# B_Main_board_v1_3.net
KiCad netlist of a schematic drawn in EAGLE
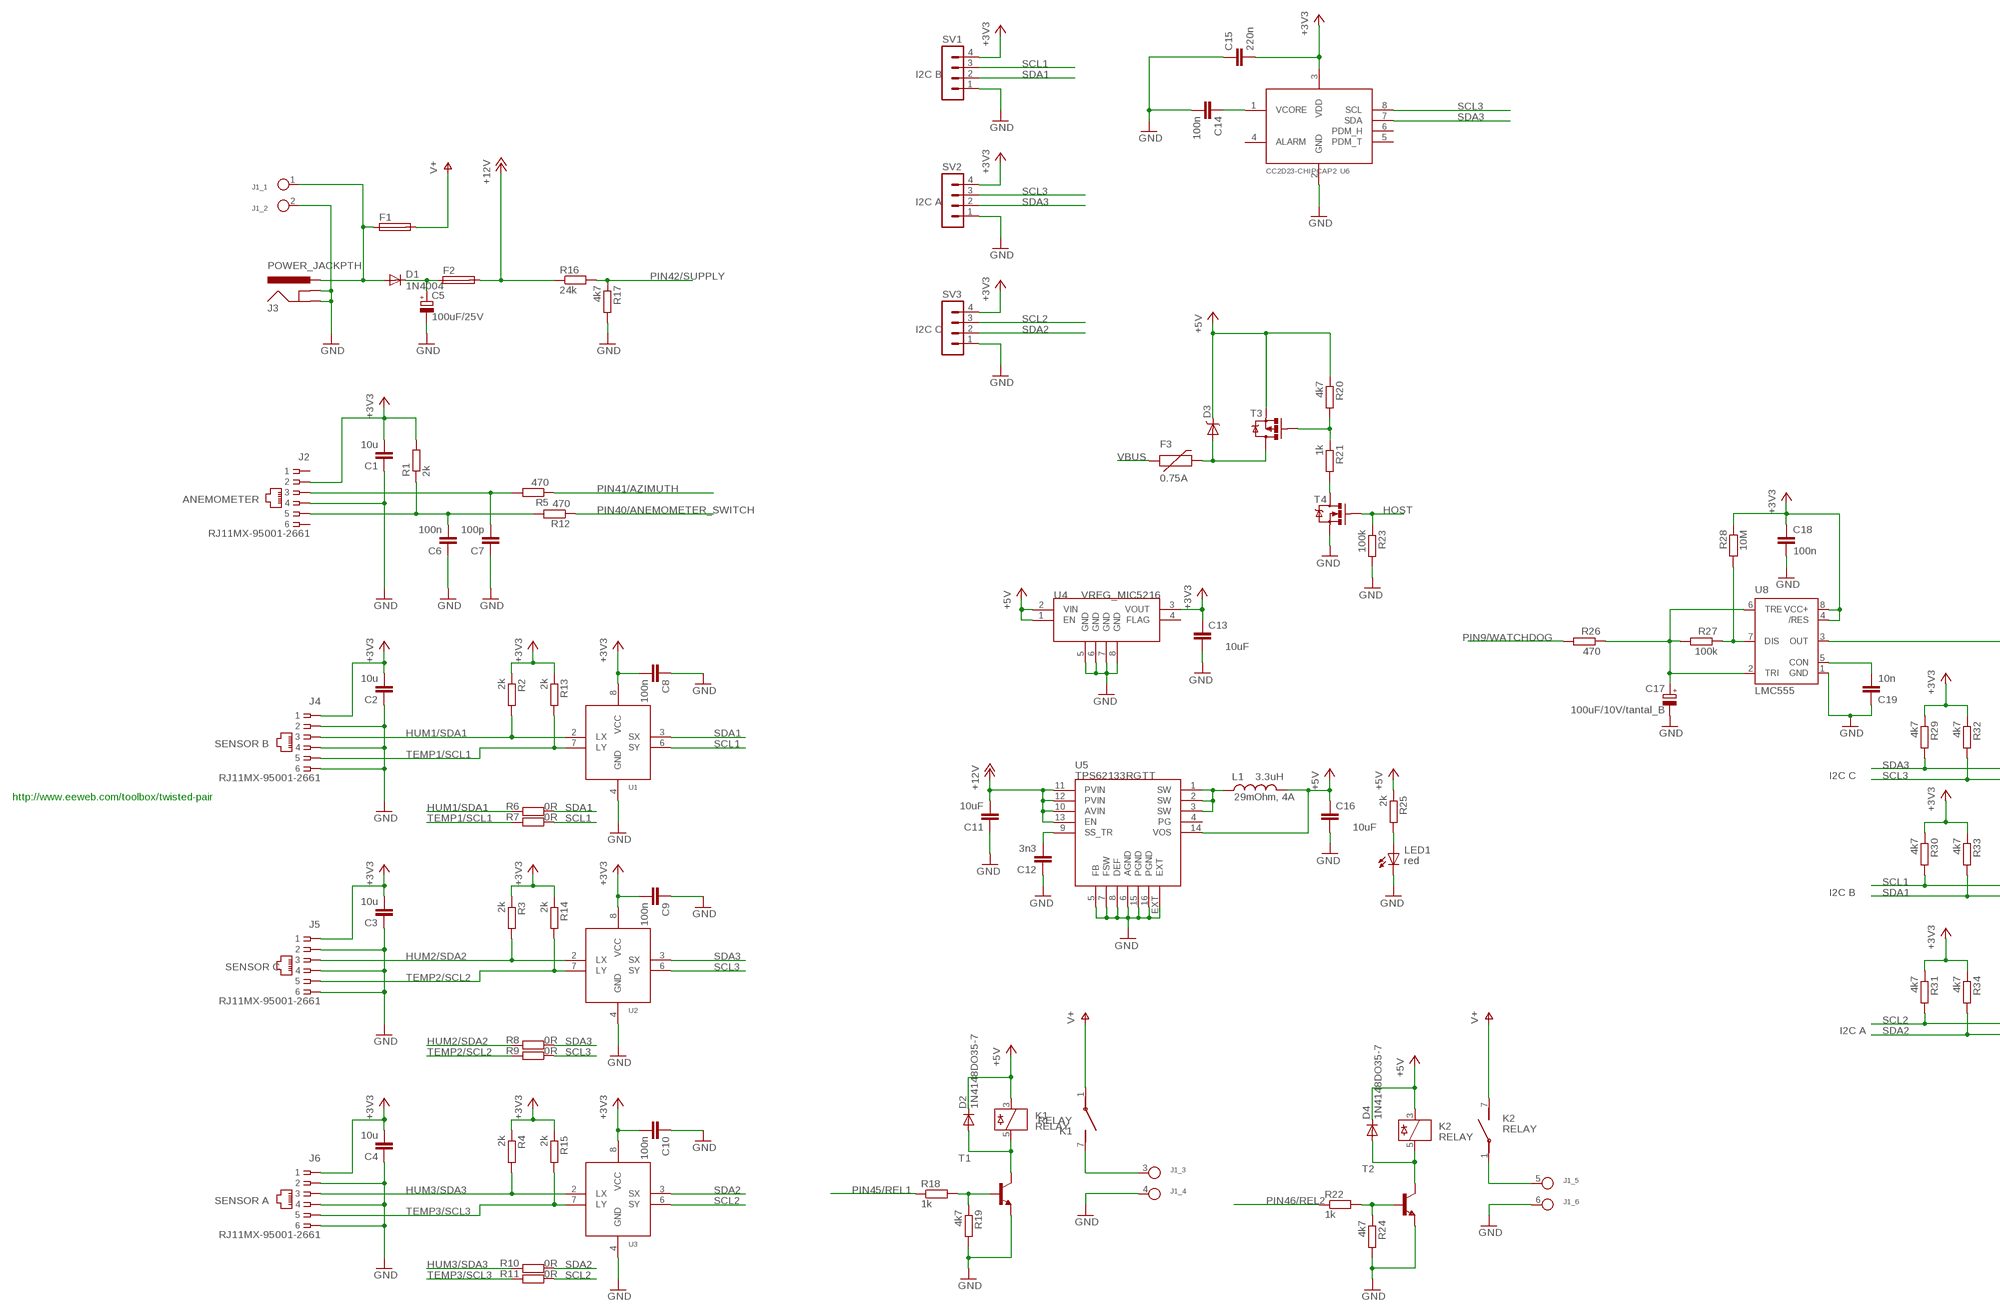
[diagram p0: schematic, sheet 1, part 1 of 2]
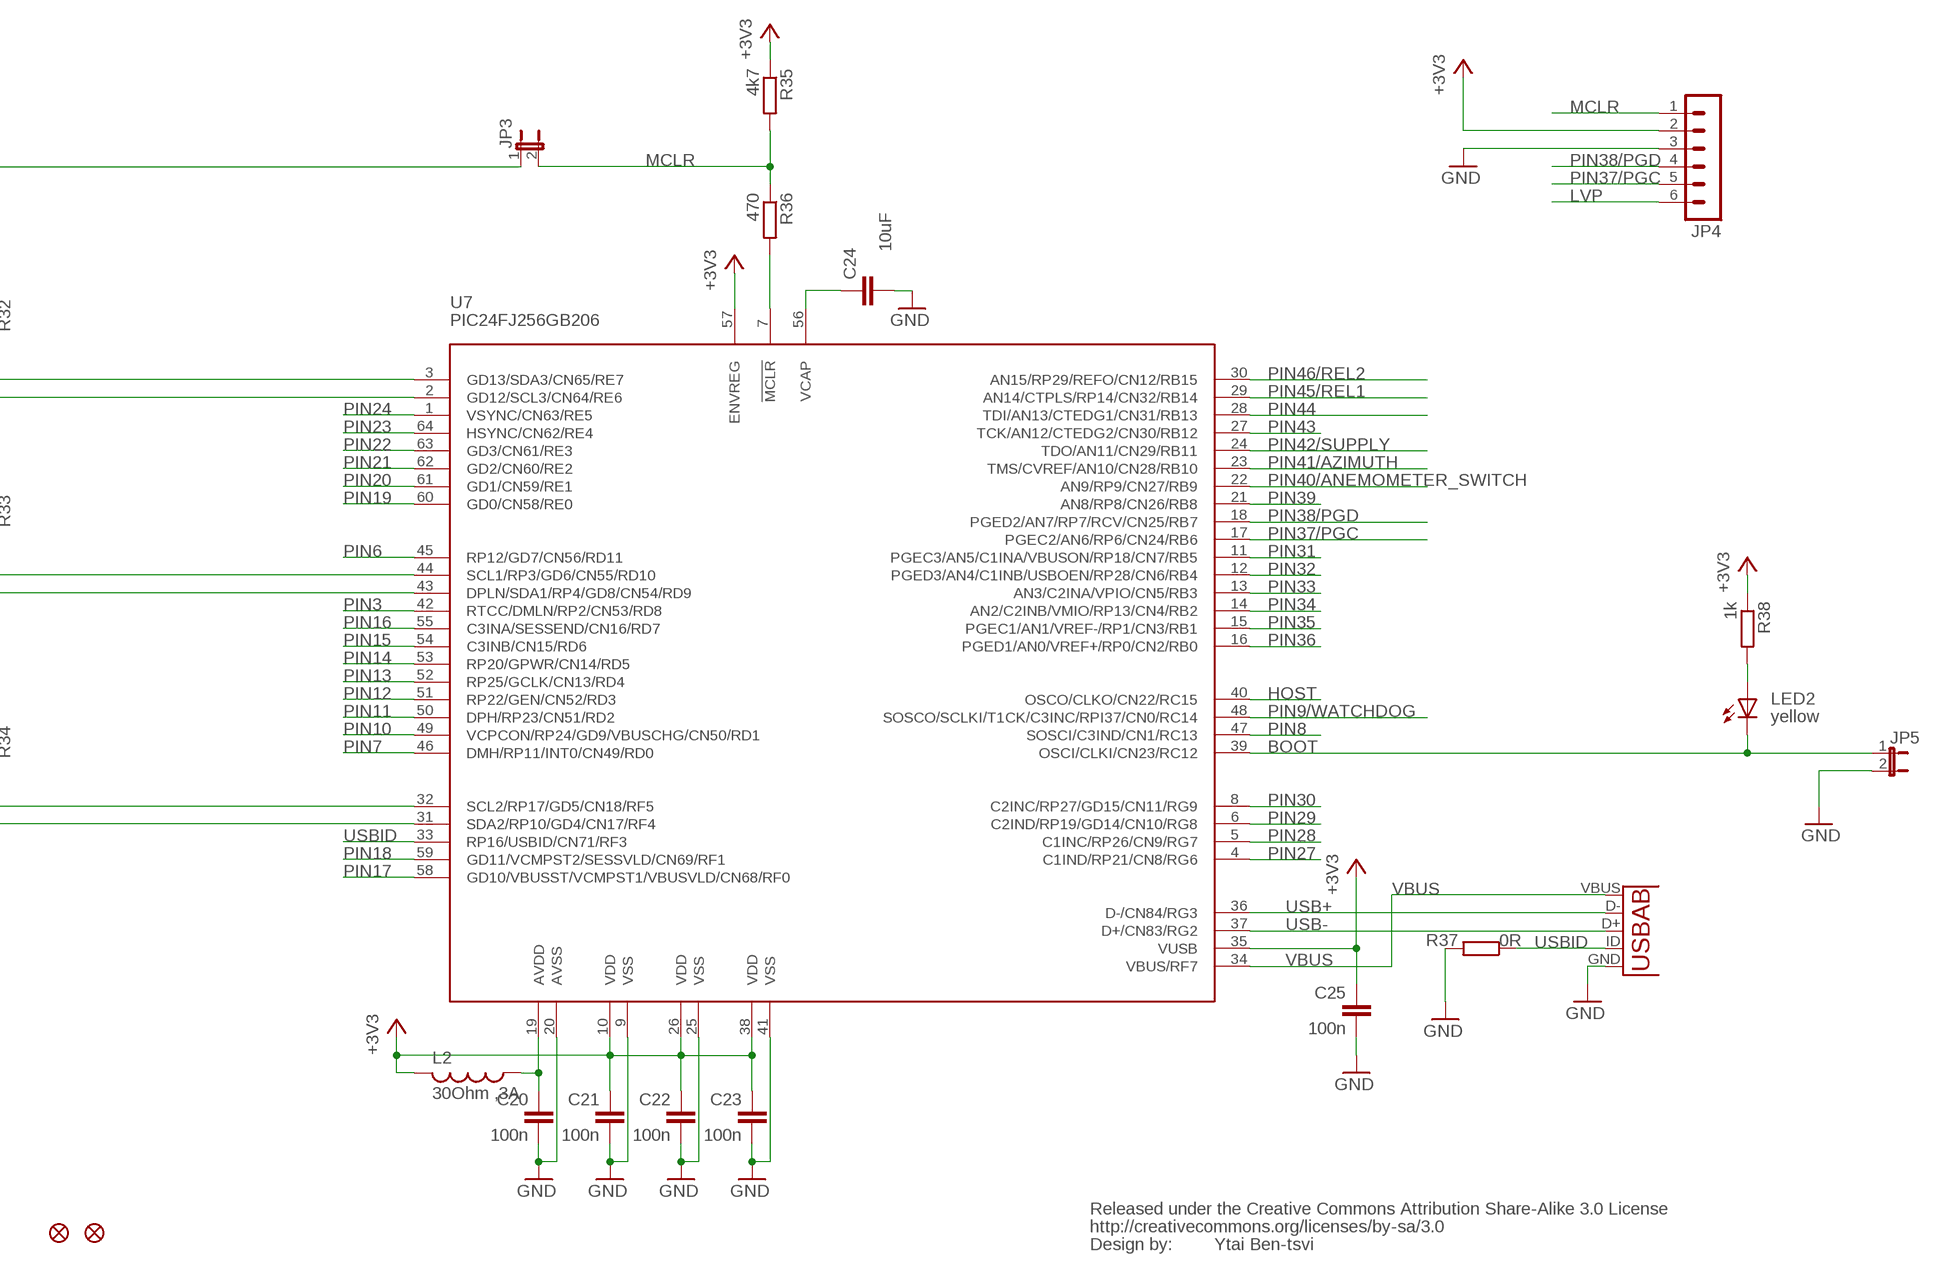
[diagram p1: schematic, sheet 1, part 2 of 2]

(export (version "E")
  (design (tool "Eeschema 10.0.6"))
  (components
    (comp (ref "C1")
      (value "10u")
      (footprint "eagle-import:C1206")
      (libsource (lib "eagle-import") (part "C-EUC1206"))
    )
    (comp (ref "C2")
      (value "10u")
      (footprint "eagle-import:C1206")
      (libsource (lib "eagle-import") (part "C-EUC1206"))
    )
    (comp (ref "C3")
      (value "10u")
      (footprint "eagle-import:C1206")
      (libsource (lib "eagle-import") (part "C-EUC1206"))
    )
    (comp (ref "C4")
      (value "10u")
      (footprint "eagle-import:C1206")
      (libsource (lib "eagle-import") (part "C-EUC1206"))
    )
    (comp (ref "C5")
      (value "100uF/25V")
      (footprint "eagle-import:E2-5")
      (libsource (lib "eagle-import") (part "CPOL-EUE2-5"))
    )
    (comp (ref "C6")
      (value "100n")
      (footprint "eagle-import:C1206")
      (libsource (lib "eagle-import") (part "C-EUC1206"))
    )
    (comp (ref "C7")
      (value "100p")
      (footprint "eagle-import:C1206")
      (libsource (lib "eagle-import") (part "C-EUC1206"))
    )
    (comp (ref "C8")
      (value "100n")
      (footprint "eagle-import:C1206")
      (libsource (lib "eagle-import") (part "C-EUC1206"))
    )
    (comp (ref "C9")
      (value "100n")
      (footprint "eagle-import:C1206")
      (libsource (lib "eagle-import") (part "C-EUC1206"))
    )
    (comp (ref "C10")
      (value "100n")
      (footprint "eagle-import:C1206")
      (libsource (lib "eagle-import") (part "C-EUC1206"))
    )
    (comp (ref "C11")
      (value "10uF")
      (footprint "eagle-import:C1206")
      (libsource (lib "eagle-import") (part "C-EUC1206"))
    )
    (comp (ref "C12")
      (value "3n3")
      (footprint "eagle-import:C1206")
      (libsource (lib "eagle-import") (part "C-EUC1206"))
    )
    (comp (ref "C13")
      (value "10uF")
      (footprint "eagle-import:C1206")
      (libsource (lib "eagle-import") (part "C-EUC1206"))
    )
    (comp (ref "C14")
      (value "100n")
      (footprint "eagle-import:C1206")
      (libsource (lib "eagle-import") (part "C-EUC1206"))
    )
    (comp (ref "C15")
      (value "220n")
      (footprint "eagle-import:C1206")
      (libsource (lib "eagle-import") (part "C-EUC1206"))
    )
    (comp (ref "C16")
      (value "10uF")
      (footprint "eagle-import:C1206")
      (libsource (lib "eagle-import") (part "C-EUC1206"))
    )
    (comp (ref "C17")
      (value "100uF/10V/tantal_B")
      (footprint "eagle-import:B_3528-21R")
      (libsource (lib "eagle-import") (part "rcl_CPOL-EUB/3528-21R"))
    )
    (comp (ref "C18")
      (value "100n")
      (footprint "eagle-import:C1206")
      (libsource (lib "eagle-import") (part "C-EUC1206"))
    )
    (comp (ref "C19")
      (value "10n")
      (footprint "eagle-import:C1206")
      (libsource (lib "eagle-import") (part "C-EUC1206"))
    )
    (comp (ref "C20")
      (value "100n")
      (footprint "eagle-import:C1206")
      (libsource (lib "eagle-import") (part "C-EUC1206"))
    )
    (comp (ref "C21")
      (value "100n")
      (footprint "eagle-import:C1206")
      (libsource (lib "eagle-import") (part "C-EUC1206"))
    )
    (comp (ref "C22")
      (value "100n")
      (footprint "eagle-import:C1206")
      (libsource (lib "eagle-import") (part "C-EUC1206"))
    )
    (comp (ref "C23")
      (value "100n")
      (footprint "eagle-import:C1206")
      (libsource (lib "eagle-import") (part "C-EUC1206"))
    )
    (comp (ref "C24")
      (value "10uF")
      (footprint "eagle-import:C1206")
      (libsource (lib "eagle-import") (part "C-EUC1206"))
    )
    (comp (ref "C25")
      (value "100n")
      (footprint "eagle-import:C1206")
      (libsource (lib "eagle-import") (part "C-EUC1206"))
    )
    (comp (ref "D1")
      (value "1N4004")
      (footprint "eagle-import:DO41-10")
      (libsource (lib "eagle-import") (part "1N4004"))
    )
    (comp (ref "D2")
      (value "1N4148DO35-7")
      (footprint "eagle-import:DO35-7")
      (libsource (lib "eagle-import") (part "1N4148DO35-7"))
    )
    (comp (ref "D3")
      (value "B340A")
      (footprint "eagle-import:SMA-DIODE")
      (fields (field (name "PART#") "B340A"))
      (libsource (lib "eagle-import") (part "DIODE-SCHOTTKY_"))
    )
    (comp (ref "D4")
      (value "1N4148DO35-7")
      (footprint "eagle-import:DO35-7")
      (libsource (lib "eagle-import") (part "1N4148DO35-7"))
    )
    (comp (ref "F1")
      (value "FUSE_HOLDER")
      (footprint "eagle-import:ZHL30")
      (libsource (lib "eagle-import") (part "FUSE_HOLDER"))
    )
    (comp (ref "F2")
      (value "FUSE_HOLDER")
      (footprint "eagle-import:ZHL30")
      (libsource (lib "eagle-import") (part "FUSE_HOLDER"))
    )
    (comp (ref "F3")
      (value "PTCSMD")
      (footprint "eagle-import:PTC-1206")
      (fields (field (name "PART#") "0ZCA0075FF2G"))
      (libsource (lib "eagle-import") (part "PTCSMD"))
    )
    (comp (ref "J1")
      (value "6P_CONN")
      (footprint "eagle-import:MOLEX_39543-0006")
      (libsource (lib "eagle-import") (part "6P_CONN"))
    )
    (comp (ref "J2")
      (value "RJ11MX-95001-2661")
      (footprint "eagle-import:MX-95001-2661")
      (libsource (lib "eagle-import") (part "RJ11MX-95001-2661"))
    )
    (comp (ref "J3")
      (value "POWER_JACKPTH")
      (footprint "eagle-import:PC-GK2.1")
      (libsource (lib "eagle-import") (part "POWER_JACKPTH"))
    )
    (comp (ref "J4")
      (value "RJ11MX-95001-2661")
      (footprint "eagle-import:MX-95001-2661")
      (libsource (lib "eagle-import") (part "RJ11MX-95001-2661"))
    )
    (comp (ref "J5")
      (value "RJ11MX-95001-2661")
      (footprint "eagle-import:MX-95001-2661")
      (libsource (lib "eagle-import") (part "RJ11MX-95001-2661"))
    )
    (comp (ref "J6")
      (value "RJ11MX-95001-2661")
      (footprint "eagle-import:MX-95001-2661")
      (libsource (lib "eagle-import") (part "RJ11MX-95001-2661"))
    )
    (comp (ref "J7")
      (value "10104111-0001LF")
      (footprint "eagle-import:USB-AB-MICRO-SMD")
      (libsource (lib "eagle-import") (part "USB_AB"))
    )
    (comp (ref "JP1")
      (value "FIDUCIALUFIDUCIAL")
      (footprint "eagle-import:MICRO-FIDUCIAL")
      (libsource (lib "eagle-import") (part "FIDUCIALUFIDUCIAL"))
    )
    (comp (ref "JP2")
      (value "FIDUCIALUFIDUCIAL")
      (footprint "eagle-import:MICRO-FIDUCIAL")
      (libsource (lib "eagle-import") (part "FIDUCIALUFIDUCIAL"))
    )
    (comp (ref "JP3")
      (value "JUMPER-2PTH")
      (footprint "eagle-import:1X02")
      (libsource (lib "eagle-import") (part "JUMPER-2PTH"))
    )
    (comp (ref "JP4")
      (value "MA06-1")
      (footprint "eagle-import:MA06-1")
      (libsource (lib "eagle-import") (part "MA06-1"))
    )
    (comp (ref "JP5")
      (value "JUMPER-2PTH")
      (footprint "eagle-import:1X02")
      (libsource (lib "eagle-import") (part "JUMPER-2PTH"))
    )
    (comp (ref "K1")
      (value "RELAY")
      (footprint "eagle-import:JV-5S-KT")
      (libsource (lib "eagle-import") (part "RELAY"))
    )
    (comp (ref "K2")
      (value "RELAY")
      (footprint "eagle-import:JV-5S-KT")
      (libsource (lib "eagle-import") (part "RELAY"))
    )
    (comp (ref "L1")
      (value "VLC5045T-3R3N")
      (footprint "eagle-import:CR54")
      (fields (field (name "AM") "3.3uH"))
      (libsource (lib "eagle-import") (part "INDUCTORCR54"))
    )
    (comp (ref "L2")
      (value "30Ohm ,3A")
      (footprint "eagle-import:R1206")
      (libsource (lib "eagle-import") (part "L-US"))
    )
    (comp (ref "LED1")
      (value "LS L29K-G1J2-1-Z")
      (footprint "eagle-import:LED-1206")
      (libsource (lib "eagle-import") (part "LED1206"))
    )
    (comp (ref "LED2")
      (value "LY L29K-J1K2-26-Z")
      (footprint "eagle-import:LED-1206")
      (libsource (lib "eagle-import") (part "LED1206"))
    )
    (comp (ref "R1")
      (value "2k")
      (footprint "eagle-import:R1206")
      (libsource (lib "eagle-import") (part "R-EU_R1206"))
    )
    (comp (ref "R2")
      (value "2k")
      (footprint "eagle-import:R1206")
      (libsource (lib "eagle-import") (part "R-EU_R1206"))
    )
    (comp (ref "R3")
      (value "2k")
      (footprint "eagle-import:R1206")
      (libsource (lib "eagle-import") (part "R-EU_R1206"))
    )
    (comp (ref "R4")
      (value "2k")
      (footprint "eagle-import:R1206")
      (libsource (lib "eagle-import") (part "R-EU_R1206"))
    )
    (comp (ref "R5")
      (value "470")
      (footprint "eagle-import:R1206")
      (libsource (lib "eagle-import") (part "R-EU_R1206"))
    )
    (comp (ref "R6")
      (value "0R")
      (footprint "eagle-import:R1206")
      (libsource (lib "eagle-import") (part "R-EU_R1206"))
    )
    (comp (ref "R7")
      (value "0R")
      (footprint "eagle-import:R1206")
      (libsource (lib "eagle-import") (part "R-EU_R1206"))
    )
    (comp (ref "R8")
      (value "0R")
      (footprint "eagle-import:R1206")
      (libsource (lib "eagle-import") (part "R-EU_R1206"))
    )
    (comp (ref "R9")
      (value "0R")
      (footprint "eagle-import:R1206")
      (libsource (lib "eagle-import") (part "R-EU_R1206"))
    )
    (comp (ref "R10")
      (value "0R")
      (footprint "eagle-import:R1206")
      (libsource (lib "eagle-import") (part "R-EU_R1206"))
    )
    (comp (ref "R11")
      (value "0R")
      (footprint "eagle-import:R1206")
      (libsource (lib "eagle-import") (part "R-EU_R1206"))
    )
    (comp (ref "R12")
      (value "470")
      (footprint "eagle-import:R1206")
      (libsource (lib "eagle-import") (part "R-EU_R1206"))
    )
    (comp (ref "R13")
      (value "2k")
      (footprint "eagle-import:R1206")
      (libsource (lib "eagle-import") (part "R-EU_R1206"))
    )
    (comp (ref "R14")
      (value "2k")
      (footprint "eagle-import:R1206")
      (libsource (lib "eagle-import") (part "R-EU_R1206"))
    )
    (comp (ref "R15")
      (value "2k")
      (footprint "eagle-import:R1206")
      (libsource (lib "eagle-import") (part "R-EU_R1206"))
    )
    (comp (ref "R16")
      (value "24k")
      (footprint "eagle-import:R1206")
      (libsource (lib "eagle-import") (part "R-EU_R1206"))
    )
    (comp (ref "R17")
      (value "4k7")
      (footprint "eagle-import:R1206")
      (libsource (lib "eagle-import") (part "R-EU_R1206"))
    )
    (comp (ref "R18")
      (value "1k")
      (footprint "eagle-import:R1206")
      (libsource (lib "eagle-import") (part "R-EU_R1206"))
    )
    (comp (ref "R19")
      (value "4k7")
      (footprint "eagle-import:R1206")
      (libsource (lib "eagle-import") (part "R-EU_R1206"))
    )
    (comp (ref "R20")
      (value "4k7")
      (footprint "eagle-import:R1206")
      (libsource (lib "eagle-import") (part "R-EU_R1206"))
    )
    (comp (ref "R21")
      (value "1k")
      (footprint "eagle-import:R1206")
      (libsource (lib "eagle-import") (part "R-EU_R1206"))
    )
    (comp (ref "R22")
      (value "1k")
      (footprint "eagle-import:R1206")
      (libsource (lib "eagle-import") (part "R-EU_R1206"))
    )
    (comp (ref "R23")
      (value "100k")
      (footprint "eagle-import:R1206")
      (libsource (lib "eagle-import") (part "R-EU_R1206"))
    )
    (comp (ref "R24")
      (value "4k7")
      (footprint "eagle-import:R1206")
      (libsource (lib "eagle-import") (part "R-EU_R1206"))
    )
    (comp (ref "R25")
      (value "2k")
      (footprint "eagle-import:R1206")
      (libsource (lib "eagle-import") (part "R-EU_R1206"))
    )
    (comp (ref "R26")
      (value "470")
      (footprint "eagle-import:R1206")
      (libsource (lib "eagle-import") (part "R-EU_R1206"))
    )
    (comp (ref "R27")
      (value "100k")
      (footprint "eagle-import:R1206")
      (libsource (lib "eagle-import") (part "R-EU_R1206"))
    )
    (comp (ref "R28")
      (value "10M")
      (footprint "eagle-import:R1206")
      (libsource (lib "eagle-import") (part "R-EU_R1206"))
    )
    (comp (ref "R29")
      (value "4k7")
      (footprint "eagle-import:R1206")
      (libsource (lib "eagle-import") (part "R-EU_R1206"))
    )
    (comp (ref "R30")
      (value "4k7")
      (footprint "eagle-import:R1206")
      (libsource (lib "eagle-import") (part "R-EU_R1206"))
    )
    (comp (ref "R31")
      (value "4k7")
      (footprint "eagle-import:R1206")
      (libsource (lib "eagle-import") (part "R-EU_R1206"))
    )
    (comp (ref "R32")
      (value "4k7")
      (footprint "eagle-import:R1206")
      (libsource (lib "eagle-import") (part "R-EU_R1206"))
    )
    (comp (ref "R33")
      (value "4k7")
      (footprint "eagle-import:R1206")
      (libsource (lib "eagle-import") (part "R-EU_R1206"))
    )
    (comp (ref "R34")
      (value "4k7")
      (footprint "eagle-import:R1206")
      (libsource (lib "eagle-import") (part "R-EU_R1206"))
    )
    (comp (ref "R35")
      (value "4k7")
      (footprint "eagle-import:R1206")
      (libsource (lib "eagle-import") (part "R-EU_R1206"))
    )
    (comp (ref "R36")
      (value "470")
      (footprint "eagle-import:R1206")
      (libsource (lib "eagle-import") (part "R-EU_R1206"))
    )
    (comp (ref "R37")
      (value "0R")
      (footprint "eagle-import:R1206")
      (libsource (lib "eagle-import") (part "R-EU_R1206"))
    )
    (comp (ref "R38")
      (value "1k")
      (footprint "eagle-import:R1206")
      (libsource (lib "eagle-import") (part "R-EU_R1206"))
    )
    (comp (ref "SV1")
      (value "MA04-1")
      (footprint "eagle-import:MA04-1")
      (libsource (lib "eagle-import") (part "MA04-1"))
    )
    (comp (ref "SV2")
      (value "MA04-1")
      (footprint "eagle-import:MA04-1")
      (libsource (lib "eagle-import") (part "MA04-1"))
    )
    (comp (ref "SV3")
      (value "MA04-1")
      (footprint "eagle-import:MA04-1")
      (libsource (lib "eagle-import") (part "MA04-1"))
    )
    (comp (ref "T1")
      (value "BC817-16-NPN-SOT23-BEC")
      (footprint "eagle-import:SOT23-BEC")
      (libsource (lib "eagle-import") (part "-NPN-SOT23-BECBC817-16"))
    )
    (comp (ref "T2")
      (value "BC817-16-NPN-SOT23-BEC")
      (footprint "eagle-import:SOT23-BEC")
      (libsource (lib "eagle-import") (part "-NPN-SOT23-BECBC817-16"))
    )
    (comp (ref "T3")
      (value "IRLML2244")
      (footprint "eagle-import:SOT23-3")
      (libsource (lib "eagle-import") (part "MOSFET-PCHANNELSMD"))
    )
    (comp (ref "T4")
      (value "2N7002PW")
      (footprint "eagle-import:SOT323")
      (fields (field (name "PART#") "2N7002PW"))
      (libsource (lib "eagle-import") (part "MOSFET-NCHANNELSOT323"))
    )
    (comp (ref "U$1")
      (value "CREATIVE_COMMONS")
      (footprint "eagle-import:CREATIVE_COMMONS")
      (libsource (lib "eagle-import") (part "CREATIVE_COMMONS"))
    )
    (comp (ref "U1")
      (value "P82B715_I2C_BUS_EXTENDER")
      (footprint "eagle-import:SO-08")
      (libsource (lib "eagle-import") (part "P82B715_I2C_BUS_EXTENDER"))
    )
    (comp (ref "U2")
      (value "P82B715_I2C_BUS_EXTENDER")
      (footprint "eagle-import:SO-08")
      (libsource (lib "eagle-import") (part "P82B715_I2C_BUS_EXTENDER"))
    )
    (comp (ref "U3")
      (value "P82B715_I2C_BUS_EXTENDER")
      (footprint "eagle-import:SO-08")
      (libsource (lib "eagle-import") (part "P82B715_I2C_BUS_EXTENDER"))
    )
    (comp (ref "U4")
      (value "VREG_MIC5216")
      (footprint "eagle-import:MSOP8")
      (libsource (lib "eagle-import") (part "VREG_MIC5216"))
    )
    (comp (ref "U5")
      (value "TPS62133RGTT")
      (footprint "eagle-import:QFN16-3X3MM")
      (libsource (lib "eagle-import") (part "TPS6214X"))
    )
    (comp (ref "U6")
      (value "CC2D23-CHIPCAP2")
      (footprint "eagle-import:CC2D23-CHIPCAP2")
      (libsource (lib "eagle-import") (part "CC2D23-CHIPCAP2"))
    )
    (comp (ref "U7")
      (value "PIC24FJ256GB206")
      (footprint "eagle-import:PIC24FXXX_TQFP64")
      (libsource (lib "eagle-import") (part "PIC24FXXXDAX06"))
    )
    (comp (ref "U8")
      (value "LMC555")
      (footprint "eagle-import:SO08")
      (libsource (lib "eagle-import") (part "NE555D"))
    )
  )
  (nets
    (net (code "1") (name "+3V3") (class "Default")
      (node (ref "C1") (pin "2") (pinfunction "2_2") (pintype "passive"))
      (node (ref "C10") (pin "2") (pinfunction "2_2") (pintype "passive"))
      (node (ref "C13") (pin "2") (pinfunction "2_2") (pintype "passive"))
      (node (ref "C15") (pin "2") (pinfunction "2_2") (pintype "passive"))
      (node (ref "C18") (pin "1") (pinfunction "1_1") (pintype "passive"))
      (node (ref "C2") (pin "2") (pinfunction "2_2") (pintype "passive"))
      (node (ref "C21") (pin "1") (pinfunction "1_1") (pintype "passive"))
      (node (ref "C22") (pin "1") (pinfunction "1_1") (pintype "passive"))
      (node (ref "C23") (pin "1") (pinfunction "1_1") (pintype "passive"))
      (node (ref "C25") (pin "1") (pinfunction "1_1") (pintype "passive"))
      (node (ref "C3") (pin "2") (pinfunction "2_2") (pintype "passive"))
      (node (ref "C4") (pin "2") (pinfunction "2_2") (pintype "passive"))
      (node (ref "C8") (pin "2") (pinfunction "2_2") (pintype "passive"))
      (node (ref "C9") (pin "2") (pinfunction "2_2") (pintype "passive"))
      (node (ref "J2") (pin "2") (pinfunction "2_2") (pintype "passive"))
      (node (ref "J4") (pin "1") (pinfunction "1_1") (pintype "passive"))
      (node (ref "J5") (pin "1") (pinfunction "1_1") (pintype "passive"))
      (node (ref "J6") (pin "1") (pinfunction "1_1") (pintype "passive"))
      (node (ref "JP4") (pin "2") (pinfunction "2_2") (pintype "passive"))
      (node (ref "L2") (pin "2") (pinfunction "2_2") (pintype "passive"))
      (node (ref "R1") (pin "2") (pinfunction "2_2") (pintype "passive"))
      (node (ref "R13") (pin "1") (pinfunction "1_1") (pintype "passive"))
      (node (ref "R14") (pin "1") (pinfunction "1_1") (pintype "passive"))
      (node (ref "R15") (pin "1") (pinfunction "1_1") (pintype "passive"))
      (node (ref "R2") (pin "1") (pinfunction "1_1") (pintype "passive"))
      (node (ref "R28") (pin "1") (pinfunction "1_1") (pintype "passive"))
      (node (ref "R29") (pin "1") (pinfunction "1_1") (pintype "passive"))
      (node (ref "R3") (pin "1") (pinfunction "1_1") (pintype "passive"))
      (node (ref "R30") (pin "1") (pinfunction "1_1") (pintype "passive"))
      (node (ref "R31") (pin "1") (pinfunction "1_1") (pintype "passive"))
      (node (ref "R32") (pin "1") (pinfunction "1_1") (pintype "passive"))
      (node (ref "R33") (pin "1") (pinfunction "1_1") (pintype "passive"))
      (node (ref "R34") (pin "1") (pinfunction "1_1") (pintype "passive"))
      (node (ref "R35") (pin "1") (pinfunction "1_1") (pintype "passive"))
      (node (ref "R38") (pin "1") (pinfunction "1_1") (pintype "passive"))
      (node (ref "R4") (pin "1") (pinfunction "1_1") (pintype "passive"))
      (node (ref "SV1") (pin "4") (pinfunction "4_4") (pintype "passive"))
      (node (ref "SV2") (pin "4") (pinfunction "4_4") (pintype "passive"))
      (node (ref "SV3") (pin "4") (pinfunction "4_4") (pintype "passive"))
      (node (ref "U1") (pin "8") (pinfunction "VCC_8") (pintype "bidirectional"))
      (node (ref "U2") (pin "8") (pinfunction "VCC_8") (pintype "bidirectional"))
      (node (ref "U3") (pin "8") (pinfunction "VCC_8") (pintype "bidirectional"))
      (node (ref "U4") (pin "3") (pinfunction "VOUT_3") (pintype "bidirectional"))
      (node (ref "U6") (pin "3") (pinfunction "VDD_3") (pintype "bidirectional"))
      (node (ref "U7") (pin "10") (pinfunction "VDD_10") (pintype "power_in"))
      (node (ref "U7") (pin "26") (pinfunction "VDD_26") (pintype "power_in"))
      (node (ref "U7") (pin "35") (pinfunction "VUSB_35") (pintype "power_in"))
      (node (ref "U7") (pin "38") (pinfunction "VDD_38") (pintype "power_in"))
      (node (ref "U7") (pin "57") (pinfunction "ENVREG_57") (pintype "input"))
      (node (ref "U8") (pin "4") (pinfunction "/RES_4") (pintype "input"))
      (node (ref "U8") (pin "8") (pinfunction "VCC+_8") (pintype "power_in"))
    )
    (net (code "2") (name "+5V") (class "Default")
      (node (ref "C16") (pin "2") (pinfunction "2_2") (pintype "passive"))
      (node (ref "D2") (pin "C") (pinfunction "C_C") (pintype "passive"))
      (node (ref "D3") (pin "C") (pinfunction "C_C") (pintype "passive"))
      (node (ref "D4") (pin "C") (pinfunction "C_C") (pintype "passive"))
      (node (ref "K1") (pin "3") (pinfunction "3_3") (pintype "passive"))
      (node (ref "K2") (pin "3") (pinfunction "3_3") (pintype "passive"))
      (node (ref "L1") (pin "P$2") (pinfunction "2_P$2") (pintype "passive"))
      (node (ref "R20") (pin "1") (pinfunction "1_1") (pintype "passive"))
      (node (ref "R25") (pin "1") (pinfunction "1_1") (pintype "passive"))
      (node (ref "T3") (pin "2") (pinfunction "S_2") (pintype "passive"))
      (node (ref "U4") (pin "1") (pinfunction "EN_1") (pintype "bidirectional"))
      (node (ref "U4") (pin "2") (pinfunction "VIN_2") (pintype "bidirectional"))
      (node (ref "U5") (pin "14") (pinfunction "VOS_14") (pintype "bidirectional"))
    )
    (net (code "3") (name "+12V") (class "Default")
      (node (ref "C11") (pin "2") (pinfunction "2_2") (pintype "passive"))
      (node (ref "F2") (pin "2") (pinfunction "2_2") (pintype "passive"))
      (node (ref "R16") (pin "1") (pinfunction "1_1") (pintype "passive"))
      (node (ref "U5") (pin "10") (pinfunction "AVIN_10") (pintype "bidirectional"))
      (node (ref "U5") (pin "11") (pinfunction "PVIN_11") (pintype "bidirectional"))
      (node (ref "U5") (pin "12") (pinfunction "PVIN_12") (pintype "bidirectional"))
      (node (ref "U5") (pin "13") (pinfunction "EN_13") (pintype "bidirectional"))
    )
    (net (code "4") (name "/BOOT") (class "Default")
      (node (ref "JP5") (pin "1") (pinfunction "1_1") (pintype "passive"))
      (node (ref "LED2") (pin "C") (pinfunction "C_C") (pintype "passive"))
      (node (ref "U7") (pin "39") (pinfunction "OSCI/CLKI/CN23/RC12_39") (pintype "bidirectional"))
    )
    (net (code "5") (name "/HOST") (class "Default")
      (node (ref "R23") (pin "1") (pinfunction "1_1") (pintype "passive"))
      (node (ref "T4") (pin "1") (pinfunction "G_1") (pintype "passive"))
      (node (ref "U7") (pin "40") (pinfunction "OSCO/CLKO/CN22/RC15_40") (pintype "bidirectional"))
    )
    (net (code "6") (name "/HUM1{slash}SDA1") (class "Default")
      (node (ref "J4") (pin "3") (pinfunction "3_3") (pintype "passive"))
      (node (ref "R2") (pin "2") (pinfunction "2_2") (pintype "passive"))
      (node (ref "R6") (pin "2") (pinfunction "2_2") (pintype "passive"))
      (node (ref "U1") (pin "2") (pinfunction "LX_2") (pintype "bidirectional"))
    )
    (net (code "7") (name "/HUM2{slash}SDA2") (class "Default")
      (node (ref "J5") (pin "3") (pinfunction "3_3") (pintype "passive"))
      (node (ref "R3") (pin "2") (pinfunction "2_2") (pintype "passive"))
      (node (ref "R8") (pin "2") (pinfunction "2_2") (pintype "passive"))
      (node (ref "U2") (pin "2") (pinfunction "LX_2") (pintype "bidirectional"))
    )
    (net (code "8") (name "/HUM3{slash}SDA3") (class "Default")
      (node (ref "J6") (pin "3") (pinfunction "3_3") (pintype "passive"))
      (node (ref "R10") (pin "2") (pinfunction "2_2") (pintype "passive"))
      (node (ref "R4") (pin "2") (pinfunction "2_2") (pintype "passive"))
      (node (ref "U3") (pin "2") (pinfunction "LX_2") (pintype "bidirectional"))
    )
    (net (code "9") (name "/LVP") (class "Default")
      (node (ref "JP4") (pin "6") (pinfunction "6_6") (pintype "passive"))
    )
    (net (code "10") (name "/MCLR") (class "Default")
      (node (ref "JP3") (pin "2") (pinfunction "2_2") (pintype "passive"))
      (node (ref "JP4") (pin "1") (pinfunction "1_1") (pintype "passive"))
      (node (ref "R35") (pin "2") (pinfunction "2_2") (pintype "passive"))
      (node (ref "R36") (pin "1") (pinfunction "1_1") (pintype "passive"))
    )
    (net (code "11") (name "/PIN3") (class "Default")
      (node (ref "U7") (pin "42") (pinfunction "RTCC/DMLN/RP2/CN53/RD8_42") (pintype "bidirectional"))
    )
    (net (code "12") (name "/PIN6") (class "Default")
      (node (ref "U7") (pin "45") (pinfunction "RP12/GD7/CN56/RD11_45") (pintype "bidirectional"))
    )
    (net (code "13") (name "/PIN7") (class "Default")
      (node (ref "U7") (pin "46") (pinfunction "DMH/RP11/INT0/CN49/RD0_46") (pintype "bidirectional"))
    )
    (net (code "14") (name "/PIN8") (class "Default")
      (node (ref "U7") (pin "47") (pinfunction "SOSCI/C3IND/CN1/RC13_47") (pintype "bidirectional"))
    )
    (net (code "15") (name "/PIN9{slash}WATCHDOG") (class "Default")
      (node (ref "R26") (pin "2") (pinfunction "2_2") (pintype "passive"))
      (node (ref "U7") (pin "48") (pinfunction "SOSCO/SCLKI/T1CK/C3INC/RPI37/CN0/RC14_48") (pintype "bidirectional"))
    )
    (net (code "16") (name "/PIN10") (class "Default")
      (node (ref "U7") (pin "49") (pinfunction "VCPCON/RP24/GD9/VBUSCHG/CN50/RD1_49") (pintype "bidirectional"))
    )
    (net (code "17") (name "/PIN11") (class "Default")
      (node (ref "U7") (pin "50") (pinfunction "DPH/RP23/CN51/RD2_50") (pintype "bidirectional"))
    )
    (net (code "18") (name "/PIN12") (class "Default")
      (node (ref "U7") (pin "51") (pinfunction "RP22/GEN/CN52/RD3_51") (pintype "bidirectional"))
    )
    (net (code "19") (name "/PIN13") (class "Default")
      (node (ref "U7") (pin "52") (pinfunction "RP25/GCLK/CN13/RD4_52") (pintype "bidirectional"))
    )
    (net (code "20") (name "/PIN14") (class "Default")
      (node (ref "U7") (pin "53") (pinfunction "RP20/GPWR/CN14/RD5_53") (pintype "bidirectional"))
    )
    (net (code "21") (name "/PIN15") (class "Default")
      (node (ref "U7") (pin "54") (pinfunction "C3INB/CN15/RD6_54") (pintype "bidirectional"))
    )
    (net (code "22") (name "/PIN16") (class "Default")
      (node (ref "U7") (pin "55") (pinfunction "C3INA/SESSEND/CN16/RD7_55") (pintype "bidirectional"))
    )
    (net (code "23") (name "/PIN17") (class "Default")
      (node (ref "U7") (pin "58") (pinfunction "GD10/VBUSST/VCMPST1/VBUSVLD/CN68/RF0_58") (pintype "bidirectional"))
    )
    (net (code "24") (name "/PIN18") (class "Default")
      (node (ref "U7") (pin "59") (pinfunction "GD11/VCMPST2/SESSVLD/CN69/RF1_59") (pintype "bidirectional"))
    )
    (net (code "25") (name "/PIN19") (class "Default")
      (node (ref "U7") (pin "60") (pinfunction "GD0/CN58/RE0_60") (pintype "bidirectional"))
    )
    (net (code "26") (name "/PIN20") (class "Default")
      (node (ref "U7") (pin "61") (pinfunction "GD1/CN59/RE1_61") (pintype "bidirectional"))
    )
    (net (code "27") (name "/PIN21") (class "Default")
      (node (ref "U7") (pin "62") (pinfunction "GD2/CN60/RE2_62") (pintype "bidirectional"))
    )
    (net (code "28") (name "/PIN22") (class "Default")
      (node (ref "U7") (pin "63") (pinfunction "GD3/CN61/RE3_63") (pintype "bidirectional"))
    )
    (net (code "29") (name "/PIN23") (class "Default")
      (node (ref "U7") (pin "64") (pinfunction "HSYNC/CN62/RE4_64") (pintype "bidirectional"))
    )
    (net (code "30") (name "/PIN24") (class "Default")
      (node (ref "U7") (pin "1") (pinfunction "VSYNC/CN63/RE5_1") (pintype "bidirectional"))
    )
    (net (code "31") (name "/PIN27") (class "Default")
      (node (ref "U7") (pin "4") (pinfunction "C1IND/RP21/CN8/RG6_4") (pintype "bidirectional"))
    )
    (net (code "32") (name "/PIN28") (class "Default")
      (node (ref "U7") (pin "5") (pinfunction "C1INC/RP26/CN9/RG7_5") (pintype "bidirectional"))
    )
    (net (code "33") (name "/PIN29") (class "Default")
      (node (ref "U7") (pin "6") (pinfunction "C2IND/RP19/GD14/CN10/RG8_6") (pintype "bidirectional"))
    )
    (net (code "34") (name "/PIN30") (class "Default")
      (node (ref "U7") (pin "8") (pinfunction "C2INC/RP27/GD15/CN11/RG9_8") (pintype "bidirectional"))
    )
    (net (code "35") (name "/PIN31") (class "Default")
      (node (ref "U7") (pin "11") (pinfunction "PGEC3/AN5/C1INA/VBUSON/RP18/CN7/RB5_11") (pintype "bidirectional"))
    )
    (net (code "36") (name "/PIN32") (class "Default")
      (node (ref "U7") (pin "12") (pinfunction "PGED3/AN4/C1INB/USBOEN/RP28/CN6/RB4_12") (pintype "bidirectional"))
    )
    (net (code "37") (name "/PIN33") (class "Default")
      (node (ref "U7") (pin "13") (pinfunction "AN3/C2INA/VPIO/CN5/RB3_13") (pintype "bidirectional"))
    )
    (net (code "38") (name "/PIN34") (class "Default")
      (node (ref "U7") (pin "14") (pinfunction "AN2/C2INB/VMIO/RP13/CN4/RB2_14") (pintype "bidirectional"))
    )
    (net (code "39") (name "/PIN35") (class "Default")
      (node (ref "U7") (pin "15") (pinfunction "PGEC1/AN1/VREF-/RP1/CN3/RB1_15") (pintype "bidirectional"))
    )
    (net (code "40") (name "/PIN36") (class "Default")
      (node (ref "U7") (pin "16") (pinfunction "PGED1/AN0/VREF+/RP0/CN2/RB0_16") (pintype "bidirectional"))
    )
    (net (code "41") (name "/PIN37{slash}PGC") (class "Default")
      (node (ref "JP4") (pin "5") (pinfunction "5_5") (pintype "passive"))
      (node (ref "U7") (pin "17") (pinfunction "PGEC2/AN6/RP6/CN24/RB6_17") (pintype "bidirectional"))
    )
    (net (code "42") (name "/PIN38{slash}PGD") (class "Default")
      (node (ref "JP4") (pin "4") (pinfunction "4_4") (pintype "passive"))
      (node (ref "U7") (pin "18") (pinfunction "PGED2/AN7/RP7/RCV/CN25/RB7_18") (pintype "bidirectional"))
    )
    (net (code "43") (name "/PIN39") (class "Default")
      (node (ref "U7") (pin "21") (pinfunction "AN8/RP8/CN26/RB8_21") (pintype "bidirectional"))
    )
    (net (code "44") (name "/PIN40{slash}ANEMOMETER_SWITCH") (class "Default")
      (node (ref "R12") (pin "1") (pinfunction "1_1") (pintype "passive"))
      (node (ref "U7") (pin "22") (pinfunction "AN9/RP9/CN27/RB9_22") (pintype "bidirectional"))
    )
    (net (code "45") (name "/PIN41{slash}AZIMUTH") (class "Default")
      (node (ref "R5") (pin "1") (pinfunction "1_1") (pintype "passive"))
      (node (ref "U7") (pin "23") (pinfunction "TMS/CVREF/AN10/CN28/RB10_23") (pintype "bidirectional"))
    )
    (net (code "46") (name "/PIN42{slash}SUPPLY") (class "Default")
      (node (ref "R16") (pin "2") (pinfunction "2_2") (pintype "passive"))
      (node (ref "R17") (pin "1") (pinfunction "1_1") (pintype "passive"))
      (node (ref "U7") (pin "24") (pinfunction "TDO/AN11/CN29/RB11_24") (pintype "bidirectional"))
    )
    (net (code "47") (name "/PIN43") (class "Default")
      (node (ref "U7") (pin "27") (pinfunction "TCK/AN12/CTEDG2/CN30/RB12_27") (pintype "bidirectional"))
    )
    (net (code "48") (name "/PIN44") (class "Default")
      (node (ref "U7") (pin "28") (pinfunction "TDI/AN13/CTEDG1/CN31/RB13_28") (pintype "bidirectional"))
    )
    (net (code "49") (name "/PIN45{slash}REL1") (class "Default")
      (node (ref "R18") (pin "1") (pinfunction "1_1") (pintype "passive"))
      (node (ref "U7") (pin "29") (pinfunction "AN14/CTPLS/RP14/CN32/RB14_29") (pintype "bidirectional"))
    )
    (net (code "50") (name "/PIN46{slash}REL2") (class "Default")
      (node (ref "R22") (pin "1") (pinfunction "1_1") (pintype "passive"))
      (node (ref "U7") (pin "30") (pinfunction "AN15/RP29/REFO/CN12/RB15_30") (pintype "bidirectional"))
    )
    (net (code "51") (name "/SCL1") (class "Default")
      (node (ref "R30") (pin "2") (pinfunction "2_2") (pintype "passive"))
      (node (ref "R7") (pin "1") (pinfunction "1_1") (pintype "passive"))
      (node (ref "SV1") (pin "3") (pinfunction "3_3") (pintype "passive"))
      (node (ref "U1") (pin "6") (pinfunction "SY_6") (pintype "bidirectional"))
      (node (ref "U7") (pin "44") (pinfunction "SCL1/RP3/GD6/CN55/RD10_44") (pintype "bidirectional"))
    )
    (net (code "52") (name "/SCL2") (class "Default")
      (node (ref "R11") (pin "1") (pinfunction "1_1") (pintype "passive"))
      (node (ref "R31") (pin "2") (pinfunction "2_2") (pintype "passive"))
      (node (ref "SV3") (pin "3") (pinfunction "3_3") (pintype "passive"))
      (node (ref "U3") (pin "6") (pinfunction "SY_6") (pintype "bidirectional"))
      (node (ref "U7") (pin "32") (pinfunction "SCL2/RP17/GD5/CN18/RF5_32") (pintype "bidirectional"))
    )
    (net (code "53") (name "/SCL3") (class "Default")
      (node (ref "R32") (pin "2") (pinfunction "2_2") (pintype "passive"))
      (node (ref "R9") (pin "1") (pinfunction "1_1") (pintype "passive"))
      (node (ref "SV2") (pin "3") (pinfunction "3_3") (pintype "passive"))
      (node (ref "U2") (pin "6") (pinfunction "SY_6") (pintype "bidirectional"))
      (node (ref "U6") (pin "8") (pinfunction "SCL_8") (pintype "bidirectional"))
      (node (ref "U7") (pin "2") (pinfunction "GD12/SCL3/CN64/RE6_2") (pintype "bidirectional"))
    )
    (net (code "54") (name "/SDA1") (class "Default")
      (node (ref "R33") (pin "2") (pinfunction "2_2") (pintype "passive"))
      (node (ref "R6") (pin "1") (pinfunction "1_1") (pintype "passive"))
      (node (ref "SV1") (pin "2") (pinfunction "2_2") (pintype "passive"))
      (node (ref "U1") (pin "3") (pinfunction "SX_3") (pintype "bidirectional"))
      (node (ref "U7") (pin "43") (pinfunction "DPLN/SDA1/RP4/GD8/CN54/RD9_43") (pintype "bidirectional"))
    )
    (net (code "55") (name "/SDA2") (class "Default")
      (node (ref "R10") (pin "1") (pinfunction "1_1") (pintype "passive"))
      (node (ref "R34") (pin "2") (pinfunction "2_2") (pintype "passive"))
      (node (ref "SV3") (pin "2") (pinfunction "2_2") (pintype "passive"))
      (node (ref "U3") (pin "3") (pinfunction "SX_3") (pintype "bidirectional"))
      (node (ref "U7") (pin "31") (pinfunction "SDA2/RP10/GD4/CN17/RF4_31") (pintype "bidirectional"))
    )
    (net (code "56") (name "/SDA3") (class "Default")
      (node (ref "R29") (pin "2") (pinfunction "2_2") (pintype "passive"))
      (node (ref "R8") (pin "1") (pinfunction "1_1") (pintype "passive"))
      (node (ref "SV2") (pin "2") (pinfunction "2_2") (pintype "passive"))
      (node (ref "U2") (pin "3") (pinfunction "SX_3") (pintype "bidirectional"))
      (node (ref "U6") (pin "7") (pinfunction "SDA_7") (pintype "bidirectional"))
      (node (ref "U7") (pin "3") (pinfunction "GD13/SDA3/CN65/RE7_3") (pintype "bidirectional"))
    )
    (net (code "57") (name "/TEMP1{slash}SCL1") (class "Default")
      (node (ref "J4") (pin "5") (pinfunction "5_5") (pintype "passive"))
      (node (ref "R13") (pin "2") (pinfunction "2_2") (pintype "passive"))
      (node (ref "R7") (pin "2") (pinfunction "2_2") (pintype "passive"))
      (node (ref "U1") (pin "7") (pinfunction "LY_7") (pintype "bidirectional"))
    )
    (net (code "58") (name "/TEMP2{slash}SCL2") (class "Default")
      (node (ref "J5") (pin "5") (pinfunction "5_5") (pintype "passive"))
      (node (ref "R14") (pin "2") (pinfunction "2_2") (pintype "passive"))
      (node (ref "R9") (pin "2") (pinfunction "2_2") (pintype "passive"))
      (node (ref "U2") (pin "7") (pinfunction "LY_7") (pintype "bidirectional"))
    )
    (net (code "59") (name "/TEMP3{slash}SCL3") (class "Default")
      (node (ref "J6") (pin "5") (pinfunction "5_5") (pintype "passive"))
      (node (ref "R11") (pin "2") (pinfunction "2_2") (pintype "passive"))
      (node (ref "R15") (pin "2") (pinfunction "2_2") (pintype "passive"))
      (node (ref "U3") (pin "7") (pinfunction "LY_7") (pintype "bidirectional"))
    )
    (net (code "60") (name "/USB+") (class "Default")
      (node (ref "J7") (pin "D-") (pinfunction "D-_D-") (pintype "bidirectional"))
      (node (ref "U7") (pin "36") (pinfunction "D-/CN84/RG3_36") (pintype "bidirectional"))
    )
    (net (code "61") (name "/USB-") (class "Default")
      (node (ref "J7") (pin "D+") (pinfunction "D+_D+") (pintype "bidirectional"))
      (node (ref "U7") (pin "37") (pinfunction "D+/CN83/RG2_37") (pintype "bidirectional"))
    )
    (net (code "62") (name "/USBID") (class "Default")
      (node (ref "J7") (pin "ID") (pinfunction "USBID_ID") (pintype "bidirectional"))
      (node (ref "R37") (pin "1") (pinfunction "1_1") (pintype "passive"))
      (node (ref "U7") (pin "33") (pinfunction "RP16/USBID/CN71/RF3_33") (pintype "bidirectional"))
    )
    (net (code "63") (name "/VBUS") (class "Default")
      (node (ref "F3") (pin "1") (pinfunction "1_1") (pintype "bidirectional"))
      (node (ref "J7") (pin "VBUS") (pinfunction "VBUS_VBUS") (pintype "bidirectional"))
      (node (ref "U7") (pin "34") (pinfunction "VBUS/RF7_34") (pintype "input"))
    )
    (net (code "64") (name "GND") (class "Default")
      (node (ref "C1") (pin "1") (pinfunction "1_1") (pintype "passive"))
      (node (ref "C10") (pin "1") (pinfunction "1_1") (pintype "passive"))
      (node (ref "C11") (pin "1") (pinfunction "1_1") (pintype "passive"))
      (node (ref "C12") (pin "1") (pinfunction "1_1") (pintype "passive"))
      (node (ref "C13") (pin "1") (pinfunction "1_1") (pintype "passive"))
      (node (ref "C14") (pin "2") (pinfunction "2_2") (pintype "passive"))
      (node (ref "C15") (pin "1") (pinfunction "1_1") (pintype "passive"))
      (node (ref "C16") (pin "1") (pinfunction "1_1") (pintype "passive"))
      (node (ref "C17") (pin "-") (pinfunction "-_-") (pintype "passive"))
      (node (ref "C18") (pin "2") (pinfunction "2_2") (pintype "passive"))
      (node (ref "C19") (pin "1") (pinfunction "1_1") (pintype "passive"))
      (node (ref "C2") (pin "1") (pinfunction "1_1") (pintype "passive"))
      (node (ref "C20") (pin "2") (pinfunction "2_2") (pintype "passive"))
      (node (ref "C21") (pin "2") (pinfunction "2_2") (pintype "passive"))
      (node (ref "C22") (pin "2") (pinfunction "2_2") (pintype "passive"))
      (node (ref "C23") (pin "2") (pinfunction "2_2") (pintype "passive"))
      (node (ref "C24") (pin "1") (pinfunction "1_1") (pintype "passive"))
      (node (ref "C25") (pin "2") (pinfunction "2_2") (pintype "passive"))
      (node (ref "C3") (pin "1") (pinfunction "1_1") (pintype "passive"))
      (node (ref "C4") (pin "1") (pinfunction "1_1") (pintype "passive"))
      (node (ref "C5") (pin "-") (pinfunction "-_-") (pintype "passive"))
      (node (ref "C6") (pin "1") (pinfunction "1_1") (pintype "passive"))
      (node (ref "C7") (pin "1") (pinfunction "1_1") (pintype "passive"))
      (node (ref "C8") (pin "1") (pinfunction "1_1") (pintype "passive"))
      (node (ref "C9") (pin "1") (pinfunction "1_1") (pintype "passive"))
      (node (ref "J1") (pin "2") (pinfunction "PIN_2") (pintype "bidirectional"))
      (node (ref "J1") (pin "4") (pinfunction "PIN_4") (pintype "bidirectional"))
      (node (ref "J1") (pin "6") (pinfunction "PIN_6") (pintype "bidirectional"))
      (node (ref "J2") (pin "4") (pinfunction "4_4") (pintype "passive"))
      (node (ref "J3") (pin "GND") (pinfunction "GND_GND") (pintype "bidirectional"))
      (node (ref "J3") (pin "GNDBREAK") (pinfunction "GNDBREAK_GNDBREAK") (pintype "bidirectional"))
      (node (ref "J4") (pin "2") (pinfunction "2_2") (pintype "passive"))
      (node (ref "J4") (pin "4") (pinfunction "4_4") (pintype "passive"))
      (node (ref "J4") (pin "6") (pinfunction "6_6") (pintype "passive"))
      (node (ref "J5") (pin "2") (pinfunction "2_2") (pintype "passive"))
      (node (ref "J5") (pin "4") (pinfunction "4_4") (pintype "passive"))
      (node (ref "J5") (pin "6") (pinfunction "6_6") (pintype "passive"))
      (node (ref "J6") (pin "2") (pinfunction "2_2") (pintype "passive"))
      (node (ref "J6") (pin "4") (pinfunction "4_4") (pintype "passive"))
      (node (ref "J6") (pin "6") (pinfunction "6_6") (pintype "passive"))
      (node (ref "J7") (pin "GND") (pinfunction "GND_GND") (pintype "bidirectional"))
      (node (ref "JP4") (pin "3") (pinfunction "3_3") (pintype "passive"))
      (node (ref "JP5") (pin "2") (pinfunction "2_2") (pintype "passive"))
      (node (ref "LED1") (pin "C") (pinfunction "C_C") (pintype "passive"))
      (node (ref "R17") (pin "2") (pinfunction "2_2") (pintype "passive"))
      (node (ref "R19") (pin "2") (pinfunction "2_2") (pintype "passive"))
      (node (ref "R23") (pin "2") (pinfunction "2_2") (pintype "passive"))
      (node (ref "R24") (pin "2") (pinfunction "2_2") (pintype "passive"))
      (node (ref "R37") (pin "2") (pinfunction "2_2") (pintype "passive"))
      (node (ref "SV1") (pin "1") (pinfunction "1_1") (pintype "passive"))
      (node (ref "SV2") (pin "1") (pinfunction "1_1") (pintype "passive"))
      (node (ref "SV3") (pin "1") (pinfunction "1_1") (pintype "passive"))
      (node (ref "T1") (pin "E") (pinfunction "E_E") (pintype "passive"))
      (node (ref "T2") (pin "E") (pinfunction "E_E") (pintype "passive"))
      (node (ref "T4") (pin "2") (pinfunction "S_2") (pintype "passive"))
      (node (ref "U1") (pin "4") (pinfunction "GND_4") (pintype "bidirectional"))
      (node (ref "U2") (pin "4") (pinfunction "GND_4") (pintype "bidirectional"))
      (node (ref "U3") (pin "4") (pinfunction "GND_4") (pintype "bidirectional"))
      (node (ref "U4") (pin "5") (pinfunction "GND_5") (pintype "bidirectional"))
      (node (ref "U4") (pin "6") (pinfunction "GND_6") (pintype "bidirectional"))
      (node (ref "U4") (pin "7") (pinfunction "GND_7") (pintype "bidirectional"))
      (node (ref "U4") (pin "8") (pinfunction "GND_8") (pintype "bidirectional"))
      (node (ref "U5") (pin "15") (pinfunction "PGND_15") (pintype "bidirectional"))
      (node (ref "U5") (pin "16") (pinfunction "PGND_16") (pintype "bidirectional"))
      (node (ref "U5") (pin "5") (pinfunction "FB_5") (pintype "bidirectional"))
      (node (ref "U5") (pin "6") (pinfunction "AGND_6") (pintype "bidirectional"))
      (node (ref "U5") (pin "7") (pinfunction "FSW_7") (pintype "bidirectional"))
      (node (ref "U5") (pin "8") (pinfunction "DEF_8") (pintype "bidirectional"))
      (node (ref "U5") (pin "EXT") (pinfunction "EXT_EXT") (pintype "bidirectional"))
      (node (ref "U6") (pin "2") (pinfunction "GND_2") (pintype "bidirectional"))
      (node (ref "U7") (pin "20") (pinfunction "AVSS_20") (pintype "power_in"))
      (node (ref "U7") (pin "25") (pinfunction "VSS_25") (pintype "power_in"))
      (node (ref "U7") (pin "41") (pinfunction "VSS_41") (pintype "power_in"))
      (node (ref "U7") (pin "9") (pinfunction "VSS_9") (pintype "power_in"))
      (node (ref "U8") (pin "1") (pinfunction "GND_1") (pintype "power_in"))
    )
    (net (code "65") (name "Net-(C5-Pad+)") (class "Default")
      (node (ref "C5") (pin "+") (pinfunction "+_+") (pintype "passive"))
      (node (ref "D1") (pin "C") (pinfunction "C_C") (pintype "passive"))
      (node (ref "F2") (pin "1") (pinfunction "1_1") (pintype "passive"))
    )
    (net (code "66") (name "Net-(C6-Pad2)") (class "Default")
      (node (ref "C6") (pin "2") (pinfunction "2_2") (pintype "passive"))
      (node (ref "J2") (pin "5") (pinfunction "5_5") (pintype "passive"))
      (node (ref "R1") (pin "1") (pinfunction "1_1") (pintype "passive"))
      (node (ref "R12") (pin "2") (pinfunction "2_2") (pintype "passive"))
    )
    (net (code "67") (name "Net-(C7-Pad2)") (class "Default")
      (node (ref "C7") (pin "2") (pinfunction "2_2") (pintype "passive"))
      (node (ref "J2") (pin "3") (pinfunction "3_3") (pintype "passive"))
      (node (ref "R5") (pin "2") (pinfunction "2_2") (pintype "passive"))
    )
    (net (code "68") (name "Net-(D2-PadA)") (class "Default")
      (node (ref "D2") (pin "A") (pinfunction "A_A") (pintype "passive"))
      (node (ref "K1") (pin "5") (pinfunction "5_5") (pintype "passive"))
      (node (ref "T1") (pin "C") (pinfunction "C_C") (pintype "passive"))
    )
    (net (code "69") (name "Net-(D4-PadA)") (class "Default")
      (node (ref "D4") (pin "A") (pinfunction "A_A") (pintype "passive"))
      (node (ref "K2") (pin "5") (pinfunction "5_5") (pintype "passive"))
      (node (ref "T2") (pin "C") (pinfunction "C_C") (pintype "passive"))
    )
    (net (code "70") (name "Net-(J1A-PIN)") (class "Default")
      (node (ref "D1") (pin "A") (pinfunction "A_A") (pintype "passive"))
      (node (ref "F1") (pin "1") (pinfunction "1_1") (pintype "passive"))
      (node (ref "J1") (pin "1") (pinfunction "PIN_1") (pintype "bidirectional"))
      (node (ref "J3") (pin "PWR") (pinfunction "PWR_PWR") (pintype "bidirectional"))
    )
    (net (code "71") (name "Net-(J1C-PIN)") (class "Default")
      (node (ref "J1") (pin "3") (pinfunction "PIN_3") (pintype "bidirectional"))
      (node (ref "K1") (pin "7") (pinfunction "S_7") (pintype "passive"))
    )
    (net (code "72") (name "Net-(J1E-PIN)") (class "Default")
      (node (ref "J1") (pin "5") (pinfunction "PIN_5") (pintype "bidirectional"))
      (node (ref "K2") (pin "1") (pinfunction "P_1") (pintype "passive"))
    )
    (net (code "73") (name "Net-(L1-1)") (class "Default")
      (node (ref "L1") (pin "P$1") (pinfunction "1_P$1") (pintype "passive"))
      (node (ref "U5") (pin "1") (pinfunction "SW_1") (pintype "bidirectional"))
      (node (ref "U5") (pin "2") (pinfunction "SW_2") (pintype "bidirectional"))
      (node (ref "U5") (pin "3") (pinfunction "SW_3") (pintype "bidirectional"))
    )
    (net (code "74") (name "Net-(LED1-PadA)") (class "Default")
      (node (ref "LED1") (pin "A") (pinfunction "A_A") (pintype "passive"))
      (node (ref "R25") (pin "2") (pinfunction "2_2") (pintype "passive"))
    )
    (net (code "75") (name "Net-(LED2-PadA)") (class "Default")
      (node (ref "LED2") (pin "A") (pinfunction "A_A") (pintype "passive"))
      (node (ref "R38") (pin "2") (pinfunction "2_2") (pintype "passive"))
    )
    (net (code "76") (name "Net-(R18-Pad2)") (class "Default")
      (node (ref "R18") (pin "2") (pinfunction "2_2") (pintype "passive"))
      (node (ref "R19") (pin "1") (pinfunction "1_1") (pintype "passive"))
      (node (ref "T1") (pin "B") (pinfunction "B_B") (pintype "passive"))
    )
    (net (code "77") (name "Net-(R22-Pad2)") (class "Default")
      (node (ref "R22") (pin "2") (pinfunction "2_2") (pintype "passive"))
      (node (ref "R24") (pin "1") (pinfunction "1_1") (pintype "passive"))
      (node (ref "T2") (pin "B") (pinfunction "B_B") (pintype "passive"))
    )
    (net (code "78") (name "Net-(T3-D)") (class "Default")
      (node (ref "D3") (pin "A") (pinfunction "A_A") (pintype "passive"))
      (node (ref "F3") (pin "2") (pinfunction "2_2") (pintype "bidirectional"))
      (node (ref "T3") (pin "3") (pinfunction "D_3") (pintype "passive"))
    )
    (net (code "79") (name "Net-(T3-G)") (class "Default")
      (node (ref "R20") (pin "2") (pinfunction "2_2") (pintype "passive"))
      (node (ref "R21") (pin "1") (pinfunction "1_1") (pintype "passive"))
      (node (ref "T3") (pin "1") (pinfunction "G_1") (pintype "passive"))
    )
    (net (code "80") (name "Net-(T4-D)") (class "Default")
      (node (ref "R21") (pin "2") (pinfunction "2_2") (pintype "passive"))
      (node (ref "T4") (pin "3") (pinfunction "D_3") (pintype "passive"))
    )
    (net (code "81") (name "Net-(U5-SS_TR)") (class "Default")
      (node (ref "C12") (pin "2") (pinfunction "2_2") (pintype "passive"))
      (node (ref "U5") (pin "9") (pinfunction "SS_TR_9") (pintype "bidirectional"))
    )
    (net (code "82") (name "Net-(U6-VCORE)") (class "Default")
      (node (ref "C14") (pin "1") (pinfunction "1_1") (pintype "passive"))
      (node (ref "U6") (pin "1") (pinfunction "VCORE_1") (pintype "bidirectional"))
    )
    (net (code "83") (name "Net-(U7-AVDD)") (class "Default")
      (node (ref "C20") (pin "1") (pinfunction "1_1") (pintype "passive"))
      (node (ref "L2") (pin "1") (pinfunction "1_1") (pintype "passive"))
      (node (ref "U7") (pin "19") (pinfunction "AVDD_19") (pintype "power_in"))
    )
    (net (code "84") (name "Net-(U7-VCAP)") (class "Default")
      (node (ref "C24") (pin "2") (pinfunction "2_2") (pintype "passive"))
      (node (ref "U7") (pin "56") (pinfunction "VCAP_56") (pintype "power_in"))
    )
    (net (code "85") (name "Net-(U7-~{MCLR})") (class "Default")
      (node (ref "R36") (pin "2") (pinfunction "2_2") (pintype "passive"))
      (node (ref "U7") (pin "7") (pinfunction "~{MCLR}_7") (pintype "input"))
    )
    (net (code "86") (name "Net-(U8-CON)") (class "Default")
      (node (ref "C19") (pin "2") (pinfunction "2_2") (pintype "passive"))
      (node (ref "U8") (pin "5") (pinfunction "CON_5") (pintype "input"))
    )
    (net (code "87") (name "Net-(U8-DIS)") (class "Default")
      (node (ref "R27") (pin "1") (pinfunction "1_1") (pintype "passive"))
      (node (ref "R28") (pin "2") (pinfunction "2_2") (pintype "passive"))
      (node (ref "U8") (pin "7") (pinfunction "DIS_7") (pintype "input"))
    )
    (net (code "88") (name "Net-(U8-OUT)") (class "Default")
      (node (ref "JP3") (pin "1") (pinfunction "1_1") (pintype "passive"))
      (node (ref "U8") (pin "3") (pinfunction "OUT_3") (pintype "output"))
    )
    (net (code "89") (name "Net-(U8-TRE)") (class "Default")
      (node (ref "C17") (pin "+") (pinfunction "+_+") (pintype "passive"))
      (node (ref "R26") (pin "1") (pinfunction "1_1") (pintype "passive"))
      (node (ref "R27") (pin "2") (pinfunction "2_2") (pintype "passive"))
      (node (ref "U8") (pin "2") (pinfunction "TRI_2") (pintype "input"))
      (node (ref "U8") (pin "6") (pinfunction "TRE_6") (pintype "input"))
    )
    (net (code "90") (name "V+") (class "Default")
      (node (ref "F1") (pin "2") (pinfunction "2_2") (pintype "passive"))
      (node (ref "K1") (pin "1") (pinfunction "P_1") (pintype "passive"))
      (node (ref "K2") (pin "7") (pinfunction "S_7") (pintype "passive"))
    )
    (net (code "91") (name "unconnected-(J2-Pad1)") (class "Default")
      (node (ref "J2") (pin "1") (pinfunction "1_1") (pintype "passive"))
    )
    (net (code "92") (name "unconnected-(J2-Pad6)") (class "Default")
      (node (ref "J2") (pin "6") (pinfunction "6_6") (pintype "passive"))
    )
    (net (code "93") (name "unconnected-(U4-FLAG-Pad4)") (class "Default")
      (node (ref "U4") (pin "4") (pinfunction "FLAG_4") (pintype "bidirectional"))
    )
    (net (code "94") (name "unconnected-(U5-PG-Pad4)") (class "Default")
      (node (ref "U5") (pin "4") (pinfunction "PG_4") (pintype "bidirectional"))
    )
    (net (code "95") (name "unconnected-(U6-ALARM-Pad4)") (class "Default")
      (node (ref "U6") (pin "4") (pinfunction "ALARM_4") (pintype "bidirectional"))
    )
    (net (code "96") (name "unconnected-(U6-PDM_H-Pad6)") (class "Default")
      (node (ref "U6") (pin "6") (pinfunction "PDM_H_6") (pintype "bidirectional"))
    )
    (net (code "97") (name "unconnected-(U6-PDM_T-Pad5)") (class "Default")
      (node (ref "U6") (pin "5") (pinfunction "PDM_T_5") (pintype "bidirectional"))
    )
  )
)
